# IR.net
KiCad netlist of a schematic drawn in Altium Designer
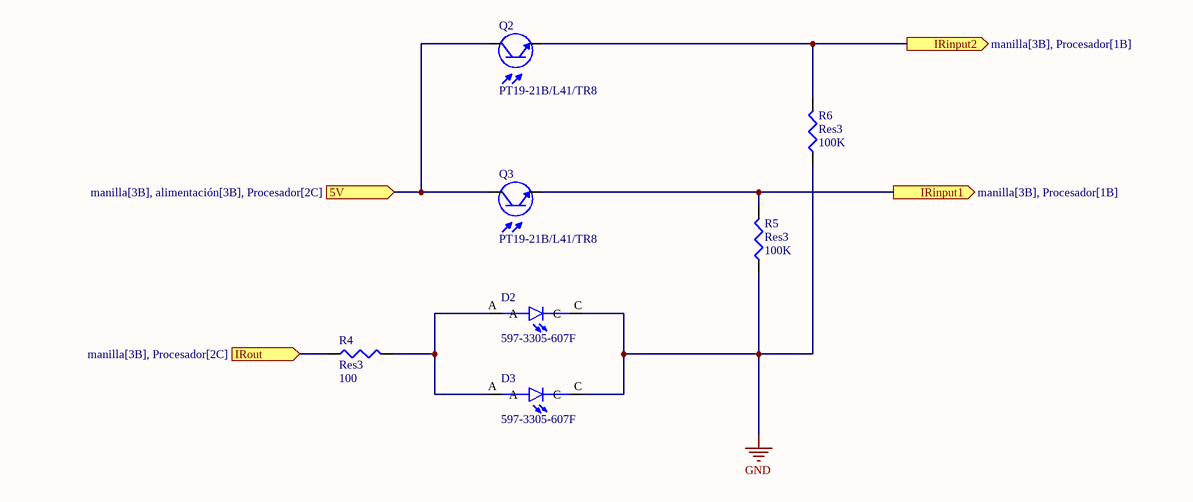
[diagram p0: IR.SchDoc]

(export (version "E")
  (design (tool "Eeschema 10.0.6"))
  (components
    (comp (ref "D2")
      (value "597-3305-607F")
      (footprint "LEDC2012X70N")
      (description "LED Uni-Color Green 4-Pin Chip 0805 T/R")
      (libsource (lib "597-3305-607F") (part "597-3305-607F"))
    )
    (comp (ref "D3")
      (value "597-3305-607F")
      (footprint "LEDC2012X70N")
      (description "LED Uni-Color Green 4-Pin Chip 0805 T/R")
      (libsource (lib "597-3305-607F") (part "597-3305-607F"))
    )
    (comp (ref "Q2")
      (value "PT19-21B/L41/TR8")
      (footprint "XDCR_PT19-21B/L41/TR8")
      (description "Phototransistors 940nm Top View 0603 (1608 Metric)")
      (libsource (lib "PT19-21B_L41_TR8") (part "PT19-21B/L41/TR8"))
    )
    (comp (ref "Q3")
      (value "PT19-21B/L41/TR8")
      (footprint "XDCR_PT19-21B/L41/TR8")
      (description "Phototransistors 940nm Top View 0603 (1608 Metric)")
      (libsource (lib "PT19-21B_L41_TR8") (part "PT19-21B/L41/TR8"))
    )
    (comp (ref "R4")
      (value "Res3")
      (footprint "J1-0603")
      (description "Resistor")
      (fields (field (name "ALTIUM_VALUE") "100") (field (name "PUBLISHER") "Altium Limited"))
      (libsource (lib "Miscellaneous Devices") (part "Res3"))
    )
    (comp (ref "R5")
      (value "Res3")
      (footprint "J1-0603")
      (description "Resistor")
      (fields (field (name "ALTIUM_VALUE") "100K") (field (name "PUBLISHER") "Altium Limited"))
      (libsource (lib "Miscellaneous Devices") (part "Res3"))
    )
    (comp (ref "R6")
      (value "Res3")
      (footprint "J1-0603")
      (description "Resistor")
      (fields (field (name "ALTIUM_VALUE") "100K") (field (name "PUBLISHER") "Altium Limited"))
      (libsource (lib "Miscellaneous Devices") (part "Res3"))
    )
  )
  (nets
    (net (code "1") (name "/5V") (class "Default")
      (node (ref "Q2") (pin "C") (pinfunction "C_C") (pintype "passive"))
      (node (ref "Q3") (pin "C") (pinfunction "C_C") (pintype "passive"))
    )
    (net (code "2") (name "/IRinput1") (class "Default")
      (node (ref "Q3") (pin "E") (pinfunction "E_E") (pintype "passive"))
      (node (ref "R5") (pin "2") (pinfunction "2_2") (pintype "passive"))
    )
    (net (code "3") (name "/IRinput2") (class "Default")
      (node (ref "Q2") (pin "E") (pinfunction "E_E") (pintype "passive"))
      (node (ref "R6") (pin "2") (pinfunction "2_2") (pintype "passive"))
    )
    (net (code "4") (name "/IRout") (class "Default")
      (node (ref "R4") (pin "1") (pinfunction "1_1") (pintype "passive"))
    )
    (net (code "5") (name "GND") (class "Default")
      (node (ref "D2") (pin "C") (pinfunction "C_C") (pintype "passive"))
      (node (ref "D3") (pin "C") (pinfunction "C_C") (pintype "passive"))
      (node (ref "R5") (pin "1") (pinfunction "1_1") (pintype "passive"))
      (node (ref "R6") (pin "1") (pinfunction "1_1") (pintype "passive"))
    )
    (net (code "6") (name "Net-(D2-PadA)") (class "Default")
      (node (ref "D2") (pin "A") (pinfunction "A_A") (pintype "passive"))
      (node (ref "D3") (pin "A") (pinfunction "A_A") (pintype "passive"))
      (node (ref "R4") (pin "2") (pinfunction "2_2") (pintype "passive"))
    )
  )
)
